# Adafruit_TLV493D.net
KiCad netlist of a schematic drawn in EAGLE
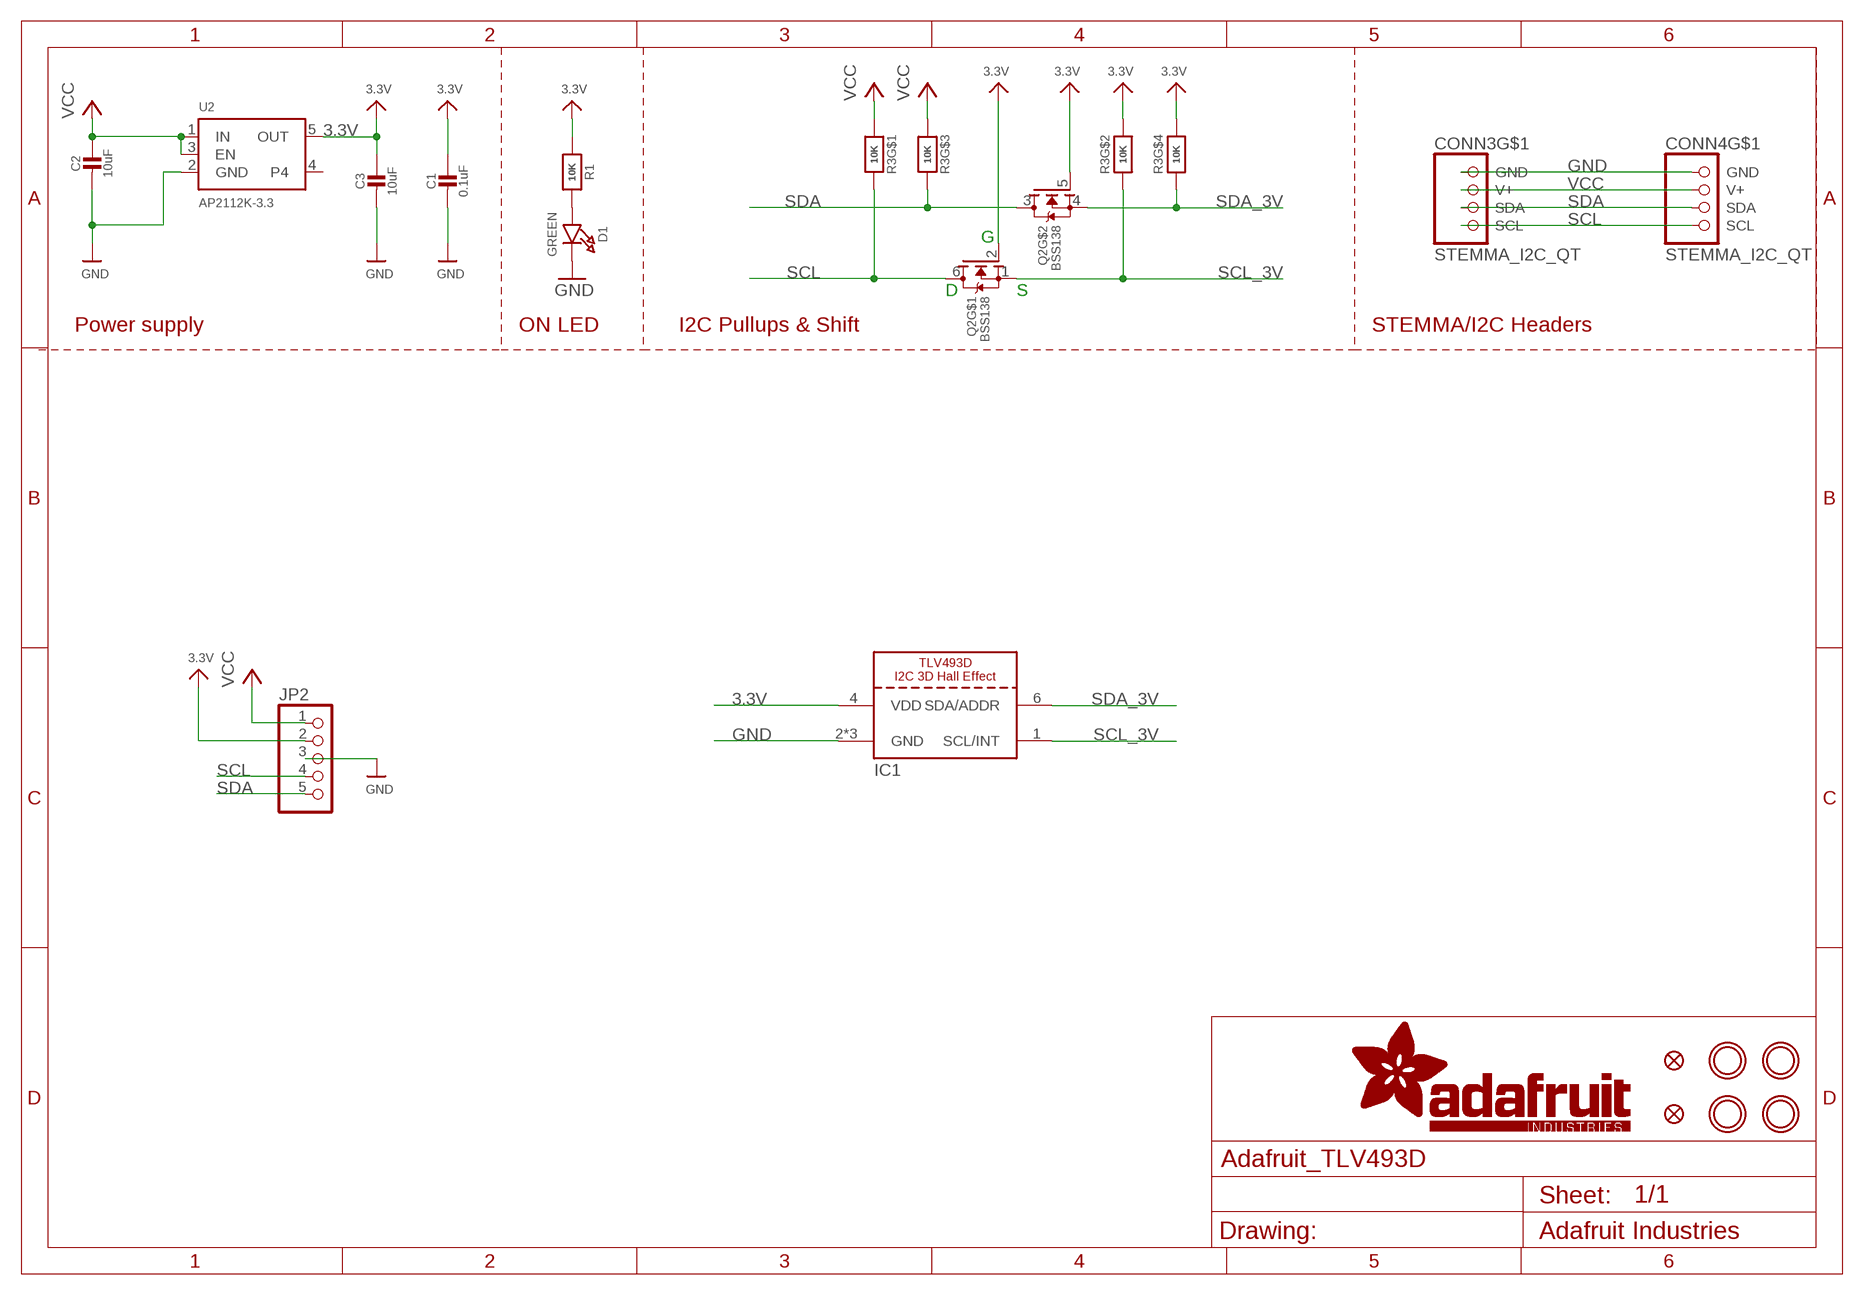
[diagram p0: schematic, sheet 1]

(export (version "E")
  (design (tool "Eeschema 10.0.6"))
  (components
    (comp (ref "C1")
      (value "0.1uF")
      (footprint "eagle-import:0603-NO")
      (libsource (lib "eagle-import") (part "CAP_CERAMIC0603_NO"))
    )
    (comp (ref "C2")
      (value "10uF")
      (footprint "eagle-import:0805-NO")
      (libsource (lib "eagle-import") (part "CAP_CERAMIC0805-NOOUTLINE"))
    )
    (comp (ref "C3")
      (value "10uF")
      (footprint "eagle-import:0805-NO")
      (libsource (lib "eagle-import") (part "CAP_CERAMIC0805-NOOUTLINE"))
    )
    (comp (ref "CONN3")
      (value "STEMMA_I2C_QT")
      (footprint "eagle-import:JST_SH4")
      (libsource (lib "eagle-import") (part "STEMMA_I2C_QT"))
    )
    (comp (ref "CONN4")
      (value "STEMMA_I2C_QT")
      (footprint "eagle-import:JST_SH4")
      (libsource (lib "eagle-import") (part "STEMMA_I2C_QT"))
    )
    (comp (ref "D1")
      (value "GREEN")
      (footprint "eagle-import:CHIPLED_0603_NOOUTLINE")
      (libsource (lib "eagle-import") (part "LED0603_NOOUTLINE"))
    )
    (comp (ref "FID3")
      (value "FIDUCIAL_1MM")
      (footprint "eagle-import:FIDUCIAL_1MM")
      (libsource (lib "eagle-import") (part "FIDUCIAL_1MM"))
    )
    (comp (ref "FID4")
      (value "FIDUCIAL_1MM")
      (footprint "eagle-import:FIDUCIAL_1MM")
      (libsource (lib "eagle-import") (part "FIDUCIAL_1MM"))
    )
    (comp (ref "IC1")
      (value "TLV493D")
      (footprint "eagle-import:SOT23-6")
      (libsource (lib "eagle-import") (part "TLV493D"))
    )
    (comp (ref "JP2")
      (value "HEADER-1X5ROUND")
      (footprint "eagle-import:1X05_ROUND")
      (libsource (lib "eagle-import") (part "HEADER-1X5ROUND"))
    )
    (comp (ref "Q2")
      (value "BSS138")
      (footprint "eagle-import:SOT363")
      (libsource (lib "eagle-import") (part "MOSFET-N_DUAL"))
    )
    (comp (ref "R1")
      (value "10K")
      (footprint "eagle-import:0603-NO")
      (libsource (lib "eagle-import") (part "RESISTOR_0603_NOOUT"))
    )
    (comp (ref "R3")
      (value "10K")
      (footprint "eagle-import:RESPACK_4X0603")
      (libsource (lib "eagle-import") (part "RESISTOR_4PACK"))
    )
    (comp (ref "U$1")
      (value "MOUNTINGHOLE2.5")
      (footprint "eagle-import:MOUNTINGHOLE_2.5_PLATED")
      (libsource (lib "eagle-import") (part "MOUNTINGHOLE2.5"))
    )
    (comp (ref "U$17")
      (value "MOUNTINGHOLE2.5")
      (footprint "eagle-import:MOUNTINGHOLE_2.5_PLATED")
      (libsource (lib "eagle-import") (part "MOUNTINGHOLE2.5"))
    )
    (comp (ref "U$19")
      (value "MOUNTINGHOLE2.5")
      (footprint "eagle-import:MOUNTINGHOLE_2.5_PLATED")
      (libsource (lib "eagle-import") (part "MOUNTINGHOLE2.5"))
    )
    (comp (ref "U$21")
      (value "MOUNTINGHOLE2.5")
      (footprint "eagle-import:MOUNTINGHOLE_2.5_PLATED")
      (libsource (lib "eagle-import") (part "MOUNTINGHOLE2.5"))
    )
    (comp (ref "U2")
      (value "AP2112K-3.3")
      (footprint "eagle-import:SOT23-5")
      (libsource (lib "eagle-import") (part "VREG_SOT23-5"))
    )
  )
  (nets
    (net (code "1") (name "/SCL") (class "Default")
      (node (ref "CONN3") (pin "4") (pinfunction "SCL_4") (pintype "passive"))
      (node (ref "CONN4") (pin "4") (pinfunction "SCL_4") (pintype "passive"))
      (node (ref "JP2") (pin "4") (pinfunction "4_4") (pintype "passive"))
      (node (ref "Q2") (pin "6") (pinfunction "D_6") (pintype "bidirectional"))
      (node (ref "R3") (pin "8") (pinfunction "2_8") (pintype "passive"))
    )
    (net (code "2") (name "/SCL_3V") (class "Default")
      (node (ref "IC1") (pin "1") (pinfunction "SCL/INT_1") (pintype "bidirectional"))
      (node (ref "Q2") (pin "1") (pinfunction "S_1") (pintype "bidirectional"))
      (node (ref "R3") (pin "7") (pinfunction "2_7") (pintype "passive"))
    )
    (net (code "3") (name "/SDA") (class "Default")
      (node (ref "CONN3") (pin "3") (pinfunction "SDA_3") (pintype "passive"))
      (node (ref "CONN4") (pin "3") (pinfunction "SDA_3") (pintype "passive"))
      (node (ref "JP2") (pin "5") (pinfunction "5_5") (pintype "passive"))
      (node (ref "Q2") (pin "3") (pinfunction "D_3") (pintype "bidirectional"))
      (node (ref "R3") (pin "6") (pinfunction "2_6") (pintype "passive"))
    )
    (net (code "4") (name "/SDA_3V") (class "Default")
      (node (ref "IC1") (pin "6") (pinfunction "SDA/ADDR_6") (pintype "bidirectional"))
      (node (ref "Q2") (pin "4") (pinfunction "S_4") (pintype "bidirectional"))
      (node (ref "R3") (pin "5") (pinfunction "2_5") (pintype "passive"))
    )
    (net (code "5") (name "3.3V") (class "Default")
      (node (ref "C1") (pin "1") (pinfunction "1_1") (pintype "passive"))
      (node (ref "C3") (pin "1") (pinfunction "1_1") (pintype "passive"))
      (node (ref "IC1") (pin "4") (pinfunction "VDD_4") (pintype "power_in"))
      (node (ref "JP2") (pin "2") (pinfunction "2_2") (pintype "passive"))
      (node (ref "Q2") (pin "2") (pinfunction "G_2") (pintype "bidirectional"))
      (node (ref "Q2") (pin "5") (pinfunction "G_5") (pintype "bidirectional"))
      (node (ref "R1") (pin "1") (pinfunction "1_1") (pintype "passive"))
      (node (ref "R3") (pin "2") (pinfunction "1_2") (pintype "passive"))
      (node (ref "R3") (pin "4") (pinfunction "1_4") (pintype "passive"))
      (node (ref "U2") (pin "5") (pinfunction "OUT_5") (pintype "power_in"))
    )
    (net (code "6") (name "GND") (class "Default")
      (node (ref "C1") (pin "2") (pinfunction "2_2") (pintype "passive"))
      (node (ref "C2") (pin "2") (pinfunction "2_2") (pintype "passive"))
      (node (ref "C3") (pin "2") (pinfunction "2_2") (pintype "passive"))
      (node (ref "CONN3") (pin "1") (pinfunction "GND_1") (pintype "passive"))
      (node (ref "CONN4") (pin "1") (pinfunction "GND_1") (pintype "passive"))
      (node (ref "D1") (pin "C") (pinfunction "C_C") (pintype "passive"))
      (node (ref "IC1") (pin "2") (pinfunction "GND_2") (pintype "power_in"))
      (node (ref "IC1") (pin "3") (pinfunction "GND_3") (pintype "power_in"))
      (node (ref "IC1") (pin "5") (pinfunction "GND_5") (pintype "power_in"))
      (node (ref "JP2") (pin "3") (pinfunction "3_3") (pintype "passive"))
      (node (ref "U2") (pin "2") (pinfunction "GND_2") (pintype "power_in"))
    )
    (net (code "7") (name "Net-(D1-PadA)") (class "Default")
      (node (ref "D1") (pin "A") (pinfunction "A_A") (pintype "passive"))
      (node (ref "R1") (pin "2") (pinfunction "2_2") (pintype "passive"))
    )
    (net (code "8") (name "VCC") (class "Default")
      (node (ref "C2") (pin "1") (pinfunction "1_1") (pintype "passive"))
      (node (ref "CONN3") (pin "2") (pinfunction "V+_2") (pintype "passive"))
      (node (ref "CONN4") (pin "2") (pinfunction "V+_2") (pintype "passive"))
      (node (ref "JP2") (pin "1") (pinfunction "1_1") (pintype "passive"))
      (node (ref "R3") (pin "1") (pinfunction "1_1") (pintype "passive"))
      (node (ref "R3") (pin "3") (pinfunction "1_3") (pintype "passive"))
      (node (ref "U2") (pin "1") (pinfunction "IN_1") (pintype "power_in"))
      (node (ref "U2") (pin "3") (pinfunction "EN_3") (pintype "input"))
    )
    (net (code "9") (name "unconnected-(U2-P4-Pad4)") (class "Default")
      (node (ref "U2") (pin "4") (pinfunction "P4_4") (pintype "bidirectional"))
    )
  )
)
